# MCU.net
KiCad netlist of a schematic drawn in Altium Designer
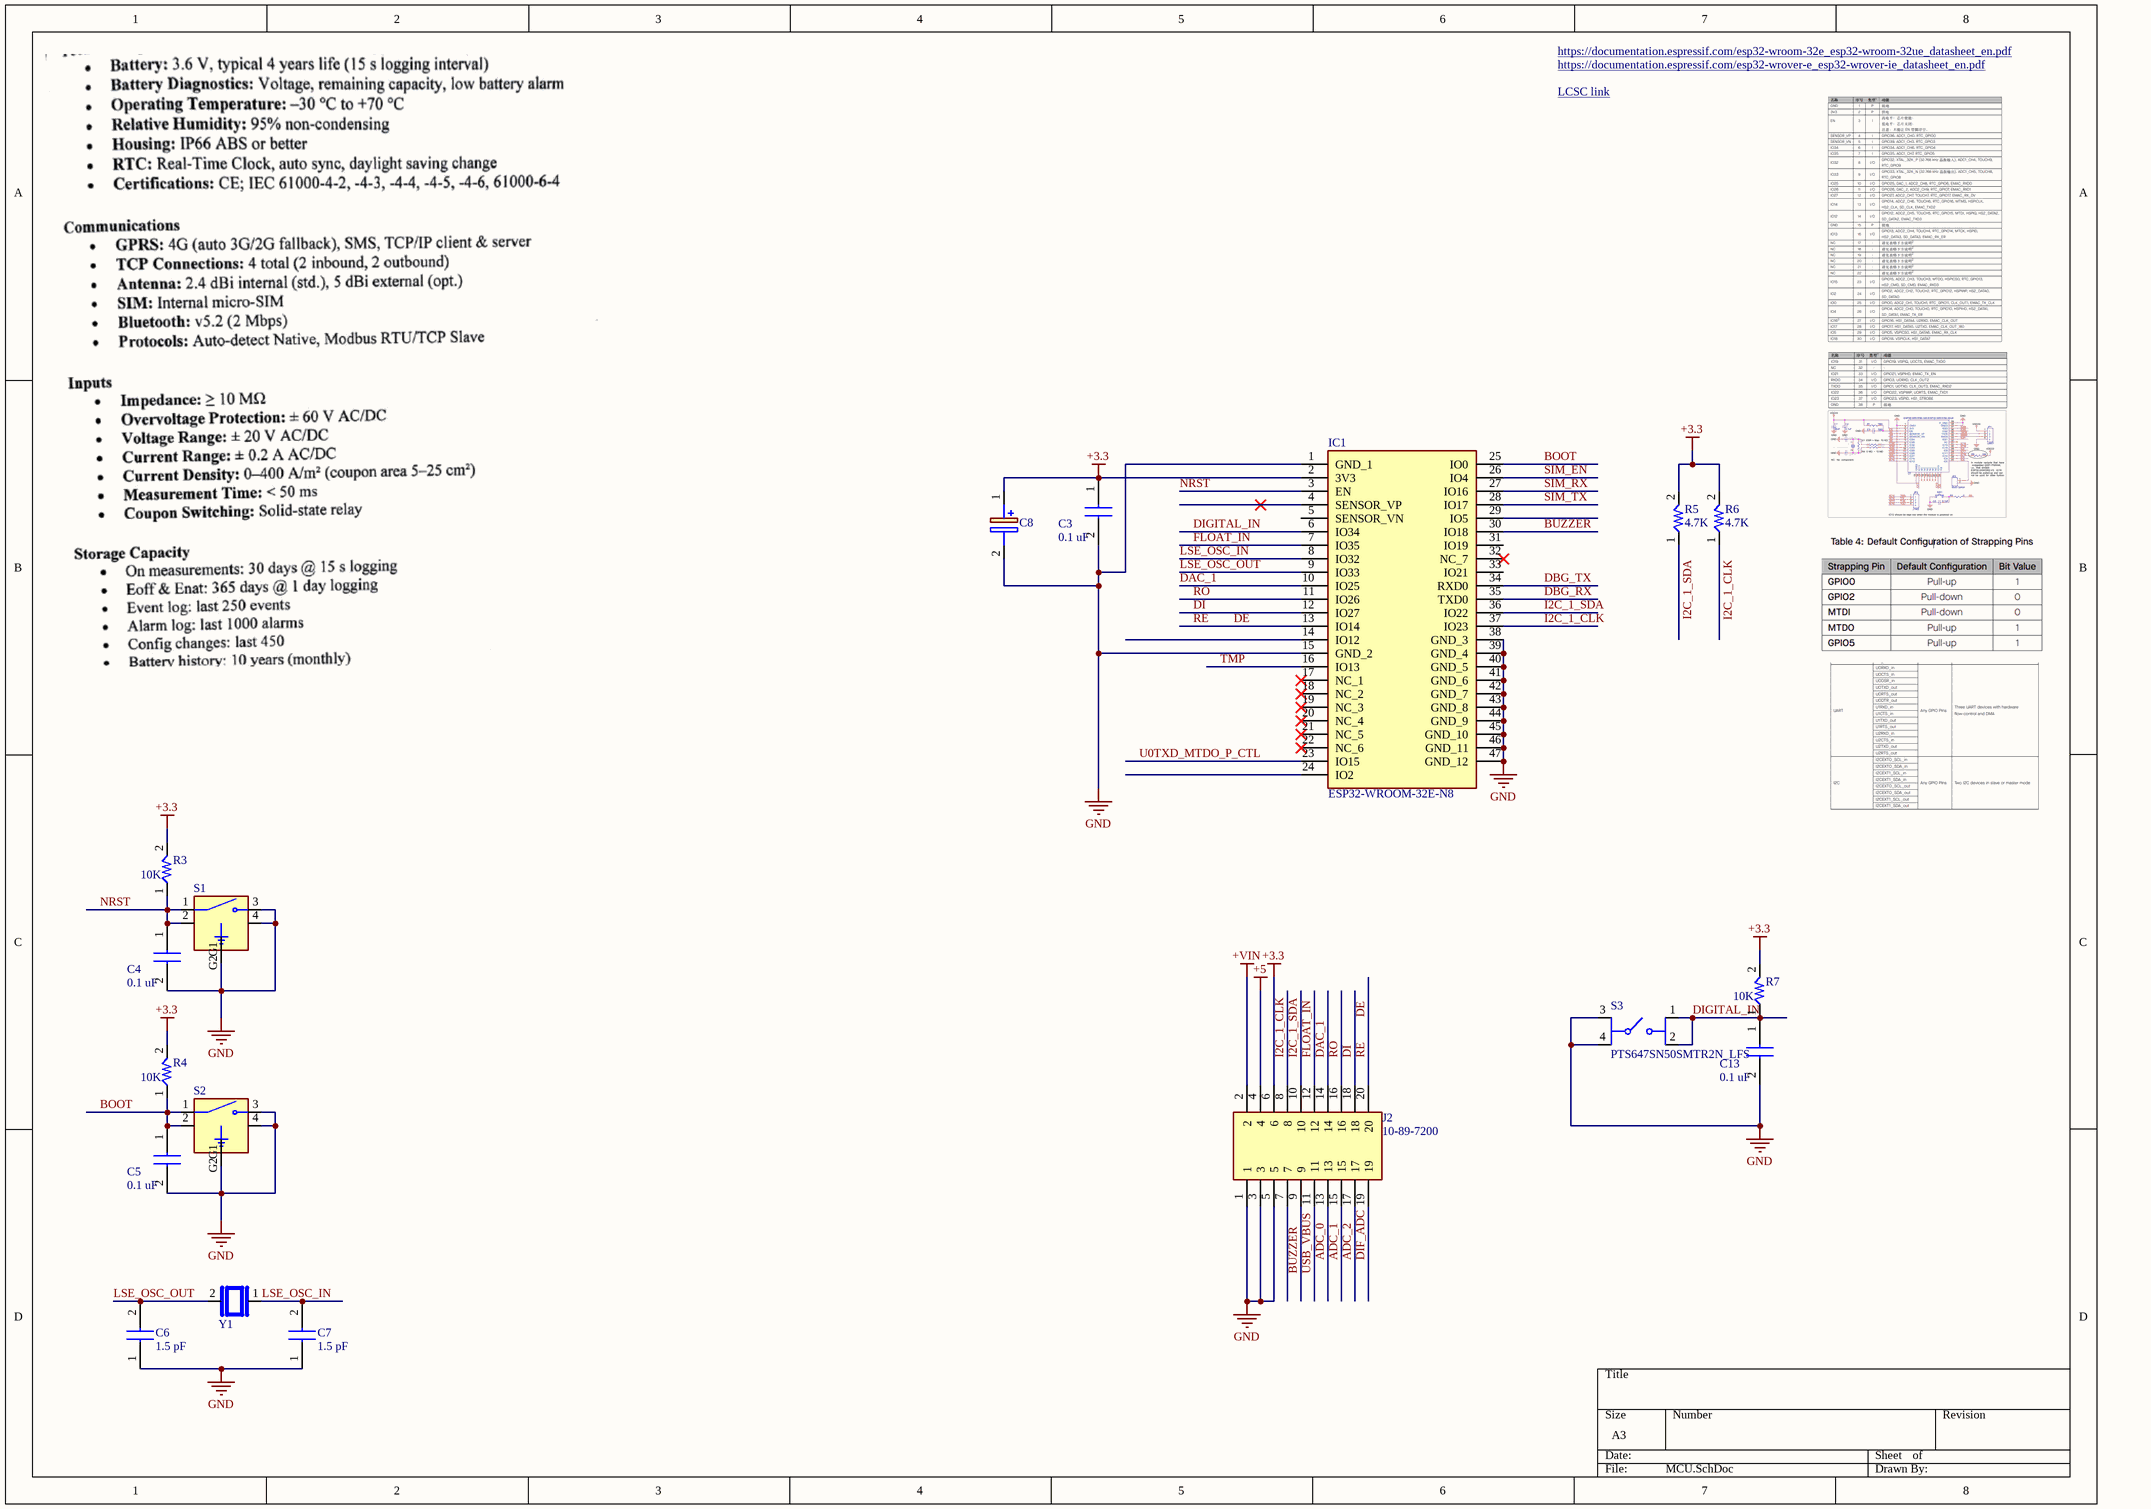
[diagram p0: MCU.SchDoc]

(export (version "E")
  (design (tool "Eeschema 10.0.6"))
  (components
    (comp (ref "C3")
      (value "0.1 uF")
      (footprint "CAP0603")
      (description "Capacitor")
      (fields
        (field (name "MANUFACTURER_PART_NUMBER") "CC0603KRX7R9BB104")
        (field (name "MOUSER PART NUMBER") "603-CC603KRX7R9BB104")
      )
      (libsource (lib "Valve_Controller_Lib") (part "CC0603KRX7R9BB104"))
    )
    (comp (ref "C4")
      (value "0.1 uF")
      (footprint "CAP0603")
      (description "Capacitor")
      (fields
        (field (name "MANUFACTURER_PART_NUMBER") "CC0603KRX7R9BB104")
        (field (name "MOUSER PART NUMBER") "603-CC603KRX7R9BB104")
      )
      (libsource (lib "Valve_Controller_Lib") (part "CC0603KRX7R9BB104"))
    )
    (comp (ref "C5")
      (value "0.1 uF")
      (footprint "CAP0603")
      (description "Capacitor")
      (fields
        (field (name "MANUFACTURER_PART_NUMBER") "CC0603KRX7R9BB104")
        (field (name "MOUSER PART NUMBER") "603-CC603KRX7R9BB104")
      )
      (libsource (lib "Valve_Controller_Lib") (part "CC0603KRX7R9BB104"))
    )
    (comp (ref "C6")
      (value "1.5 pF")
      (footprint "CAP0603")
      (description "Capacitor")
      (fields
        (field (name "MANUFACTURER_PART_NUMBER") "CC0603KRX7R9BB104")
        (field (name "MOUSER PART NUMBER") "603-CC603KRX7R9BB104")
      )
      (libsource (lib "Valve_Controller_Lib") (part "CC0603KRX7R9BB104"))
    )
    (comp (ref "C7")
      (value "1.5 pF")
      (footprint "CAP0603")
      (description "Capacitor")
      (fields
        (field (name "MANUFACTURER_PART_NUMBER") "CC0603KRX7R9BB104")
        (field (name "MOUSER PART NUMBER") "603-CC603KRX7R9BB104")
      )
      (libsource (lib "Valve_Controller_Lib") (part "CC0603KRX7R9BB104"))
    )
    (comp (ref "C8")
      (value "TPSD227K010R0100")
      (footprint "SamacSys:CAPPM7344X310N")
      (description "Capacitor Polarised")
      (fields (field (name "MOUSER PART NUMBER") "581-TPSD227K010R0100"))
      (libsource (lib "*") (part "TPSD227K010R0100"))
    )
    (comp (ref "C13")
      (value "0.1 uF")
      (footprint "CAP0603")
      (description "Capacitor")
      (fields
        (field (name "MANUFACTURER_PART_NUMBER") "CC0603KRX7R9BB104")
        (field (name "MOUSER PART NUMBER") "603-CC603KRX7R9BB104")
      )
      (libsource (lib "Valve_Controller_Lib") (part "CC0603KRX7R9BB104"))
    )
    (comp (ref "IC1")
      (value "ESP32-WROOM-32E-N8")
      (footprint "SamacSys:ESP32WROOM32EN8")
      (description "Integrated Circuit")
      (fields (field (name "MOUSER PART NUMBER") "356-ESP32WRM32E164PH"))
      (libsource (lib "*") (part "ESP32-WROOM-32E-N8"))
    )
    (comp (ref "J2")
      (value "10-89-7200")
      (footprint "SamacSys:HDRV20W87P254_2X10_2553X508X864P")
      (description "Connector")
      (fields (field (name "MOUSER PART NUMBER") "538-10-89-7200"))
      (libsource (lib "*") (part "10-89-7200"))
    )
    (comp (ref "R3")
      (value "10K")
      (footprint "RES0603")
      (description "Resistor")
      (fields (field (name "MANUFACTURER_PART_NUMBER") "0603WAF1001T5E"))
      (libsource (lib "Valve_Controller_Lib") (part "RES"))
    )
    (comp (ref "R4")
      (value "10K")
      (footprint "RES0603")
      (description "Resistor")
      (fields (field (name "MANUFACTURER_PART_NUMBER") "0603WAF1001T5E"))
      (libsource (lib "Valve_Controller_Lib") (part "RES"))
    )
    (comp (ref "R5")
      (value "4.7K")
      (footprint "RES0603")
      (description "Resistor")
      (fields (field (name "MANUFACTURER_PART_NUMBER") "0603WAF1001T5E"))
      (libsource (lib "Valve_Controller_Lib") (part "RES"))
    )
    (comp (ref "R6")
      (value "4.7K")
      (footprint "RES0603")
      (description "Resistor")
      (fields (field (name "MANUFACTURER_PART_NUMBER") "0603WAF1001T5E"))
      (libsource (lib "Valve_Controller_Lib") (part "RES"))
    )
    (comp (ref "R7")
      (value "10K")
      (footprint "RES0603")
      (description "Resistor")
      (fields (field (name "MANUFACTURER_PART_NUMBER") "0603WAF1001T5E"))
      (libsource (lib "Valve_Controller_Lib") (part "RES"))
    )
    (comp (ref "S1")
      (value "PTS526_SMG15_SMTR2_LFS")
      (footprint "SW_PTS526_SMG15_SMTR2_LFS")
      (description "Tactile Switch SPST-NO Top Actuated Surface Mount")
      (fields (field (name "MP") "PTS526 SMG15 SMTR2 LFS") (field (name "MF") "C&K"))
      (libsource (lib "Valve_Controller_Lib") (part "PTS526_SMG15_SMTR2_LFS"))
    )
    (comp (ref "S2")
      (value "PTS526_SMG15_SMTR2_LFS")
      (footprint "SW_PTS526_SMG15_SMTR2_LFS")
      (description "Tactile Switch SPST-NO Top Actuated Surface Mount")
      (fields (field (name "MP") "PTS526 SMG15 SMTR2 LFS") (field (name "MF") "C&K"))
      (libsource (lib "Valve_Controller_Lib") (part "PTS526_SMG15_SMTR2_LFS"))
    )
    (comp (ref "S3")
      (value "PTS647SN50SMTR2N_LFS")
      (footprint "SamacSys:PTS647SK50SMTR2LFS")
      (description "Switch (4-Pin Push)")
      (fields (field (name "MANUFACTURER_PART_NUMBER") "PTS647SN50SMTR2N LFS"))
      (libsource (lib "*") (part "PTS647SN50SMTR2N_LFS"))
    )
    (comp (ref "Y1")
      (value "CM8V-T1A-32.768KHZ-6PF-20PPM-TA-QC")
      (footprint "XTAL_CM8V-T1A-32.768KHZ-6PF-20PPM-TA-QC")
      (description "Tuning Fork Crystal 32.768kHz in SMD 1.2 x 2.0mm package")
      (fields (field (name "MF") "Micro Crystal") (field (name "MP") "CM8V-T1A-32.768kHz-6pF-20PPM-TA-QC"))
      (libsource (lib "Valve_Controller_Lib") (part "CM8V-T1A-32.768KHZ-6PF-20PPM-TA-QC"))
    )
  )
  (nets
    (net (code "1") (name "+3.3") (class "Default")
      (node (ref "C3") (pin "1") (pinfunction "1_1") (pintype "passive"))
      (node (ref "C8") (pin "1") (pinfunction "+_1") (pintype "passive"))
      (node (ref "IC1") (pin "2") (pinfunction "3V3_2") (pintype "passive"))
      (node (ref "J2") (pin "6") (pinfunction "6_6") (pintype "passive"))
      (node (ref "R3") (pin "2") (pinfunction "2_2") (pintype "passive"))
      (node (ref "R4") (pin "2") (pinfunction "2_2") (pintype "passive"))
      (node (ref "R5") (pin "2") (pinfunction "2_2") (pintype "passive"))
      (node (ref "R6") (pin "2") (pinfunction "2_2") (pintype "passive"))
      (node (ref "R7") (pin "2") (pinfunction "2_2") (pintype "passive"))
    )
    (net (code "2") (name "+5") (class "Default")
      (node (ref "J2") (pin "4") (pinfunction "4_4") (pintype "passive"))
    )
    (net (code "3") (name "+VIN") (class "Default")
      (node (ref "J2") (pin "2") (pinfunction "2_2") (pintype "passive"))
    )
    (net (code "4") (name "/ADC_0") (class "Default")
      (node (ref "J2") (pin "13") (pinfunction "13_13") (pintype "passive"))
    )
    (net (code "5") (name "/ADC_1") (class "Default")
      (node (ref "J2") (pin "15") (pinfunction "15_15") (pintype "passive"))
    )
    (net (code "6") (name "/ADC_2") (class "Default")
      (node (ref "J2") (pin "17") (pinfunction "17_17") (pintype "passive"))
    )
    (net (code "7") (name "/BOOT") (class "Default")
      (node (ref "C5") (pin "1") (pinfunction "1_1") (pintype "passive"))
      (node (ref "IC1") (pin "25") (pinfunction "IO0_25") (pintype "passive"))
      (node (ref "R4") (pin "1") (pinfunction "1_1") (pintype "passive"))
      (node (ref "S2") (pin "1") (pinfunction "COM_1") (pintype "passive"))
      (node (ref "S2") (pin "2") (pinfunction "COM_2") (pintype "passive"))
    )
    (net (code "8") (name "/BUZZER") (class "Default")
      (node (ref "IC1") (pin "30") (pinfunction "IO18_30") (pintype "passive"))
      (node (ref "J2") (pin "9") (pinfunction "9_9") (pintype "passive"))
    )
    (net (code "9") (name "/DAC_1") (class "Default")
      (node (ref "IC1") (pin "10") (pinfunction "IO25_10") (pintype "passive"))
      (node (ref "J2") (pin "14") (pinfunction "14_14") (pintype "passive"))
    )
    (net (code "10") (name "/DBG_RX") (class "Default")
      (node (ref "IC1") (pin "35") (pinfunction "TXD0_35") (pintype "passive"))
    )
    (net (code "11") (name "/DBG_TX") (class "Default")
      (node (ref "IC1") (pin "34") (pinfunction "RXD0_34") (pintype "passive"))
    )
    (net (code "12") (name "/DE") (class "Default")
      (node (ref "IC1") (pin "13") (pinfunction "IO14_13") (pintype "passive"))
      (node (ref "J2") (pin "20") (pinfunction "20_20") (pintype "passive"))
    )
    (net (code "13") (name "/DI") (class "Default")
      (node (ref "IC1") (pin "12") (pinfunction "IO27_12") (pintype "passive"))
      (node (ref "J2") (pin "18") (pinfunction "18_18") (pintype "passive"))
    )
    (net (code "14") (name "/DIF_ADC") (class "Default")
      (node (ref "J2") (pin "19") (pinfunction "19_19") (pintype "passive"))
    )
    (net (code "15") (name "/DIGITAL_IN") (class "Default")
      (node (ref "C13") (pin "1") (pinfunction "1_1") (pintype "passive"))
      (node (ref "IC1") (pin "6") (pinfunction "IO34_6") (pintype "passive"))
      (node (ref "R7") (pin "1") (pinfunction "1_1") (pintype "passive"))
      (node (ref "S3") (pin "1") (pinfunction "NO_1_1") (pintype "passive"))
      (node (ref "S3") (pin "2") (pinfunction "NO_2_2") (pintype "passive"))
    )
    (net (code "16") (name "/FLOAT_IN") (class "Default")
      (node (ref "IC1") (pin "7") (pinfunction "IO35_7") (pintype "passive"))
      (node (ref "J2") (pin "12") (pinfunction "12_12") (pintype "passive"))
    )
    (net (code "17") (name "/I2C_1_CLK") (class "Default")
      (node (ref "IC1") (pin "37") (pinfunction "IO23_37") (pintype "passive"))
      (node (ref "J2") (pin "8") (pinfunction "8_8") (pintype "passive"))
      (node (ref "R6") (pin "1") (pinfunction "1_1") (pintype "passive"))
    )
    (net (code "18") (name "/I2C_1_SDA") (class "Default")
      (node (ref "IC1") (pin "36") (pinfunction "IO22_36") (pintype "passive"))
      (node (ref "J2") (pin "10") (pinfunction "10_10") (pintype "passive"))
      (node (ref "R5") (pin "1") (pinfunction "1_1") (pintype "passive"))
    )
    (net (code "19") (name "/LSE_OSC_IN") (class "Default")
      (node (ref "C7") (pin "2") (pinfunction "2_2") (pintype "passive"))
      (node (ref "IC1") (pin "8") (pinfunction "IO32_8") (pintype "passive"))
      (node (ref "Y1") (pin "1") (pinfunction "1_1") (pintype "passive"))
    )
    (net (code "20") (name "/LSE_OSC_OUT") (class "Default")
      (node (ref "C6") (pin "2") (pinfunction "2_2") (pintype "passive"))
      (node (ref "IC1") (pin "9") (pinfunction "IO33_9") (pintype "passive"))
      (node (ref "Y1") (pin "2") (pinfunction "2_2") (pintype "passive"))
    )
    (net (code "21") (name "/NRST") (class "Default")
      (node (ref "C4") (pin "1") (pinfunction "1_1") (pintype "passive"))
      (node (ref "IC1") (pin "3") (pinfunction "EN_3") (pintype "passive"))
      (node (ref "R3") (pin "1") (pinfunction "1_1") (pintype "passive"))
      (node (ref "S1") (pin "1") (pinfunction "COM_1") (pintype "passive"))
      (node (ref "S1") (pin "2") (pinfunction "COM_2") (pintype "passive"))
    )
    (net (code "22") (name "/RO") (class "Default")
      (node (ref "IC1") (pin "11") (pinfunction "IO26_11") (pintype "passive"))
      (node (ref "J2") (pin "16") (pinfunction "16_16") (pintype "passive"))
    )
    (net (code "23") (name "/SIM_EN") (class "Default")
      (node (ref "IC1") (pin "26") (pinfunction "IO4_26") (pintype "passive"))
    )
    (net (code "24") (name "/SIM_RX") (class "Default")
      (node (ref "IC1") (pin "27") (pinfunction "IO16_27") (pintype "passive"))
    )
    (net (code "25") (name "/SIM_TX") (class "Default")
      (node (ref "IC1") (pin "28") (pinfunction "IO17_28") (pintype "passive"))
    )
    (net (code "26") (name "/TMP") (class "Default")
      (node (ref "IC1") (pin "16") (pinfunction "IO13_16") (pintype "passive"))
    )
    (net (code "27") (name "/U0TXD_MTDO_P_CTL") (class "Default")
      (node (ref "IC1") (pin "23") (pinfunction "IO15_23") (pintype "passive"))
    )
    (net (code "28") (name "/USB_VBUS") (class "Default")
      (node (ref "J2") (pin "11") (pinfunction "11_11") (pintype "passive"))
    )
    (net (code "29") (name "GND") (class "Default")
      (node (ref "C13") (pin "2") (pinfunction "2_2") (pintype "passive"))
      (node (ref "C3") (pin "2") (pinfunction "2_2") (pintype "passive"))
      (node (ref "C4") (pin "2") (pinfunction "2_2") (pintype "passive"))
      (node (ref "C5") (pin "2") (pinfunction "2_2") (pintype "passive"))
      (node (ref "C6") (pin "1") (pinfunction "1_1") (pintype "passive"))
      (node (ref "C7") (pin "1") (pinfunction "1_1") (pintype "passive"))
      (node (ref "C8") (pin "2") (pinfunction "-_2") (pintype "passive"))
      (node (ref "IC1") (pin "1") (pinfunction "GND_1_1") (pintype "passive"))
      (node (ref "IC1") (pin "15") (pinfunction "GND_2_15") (pintype "passive"))
      (node (ref "IC1") (pin "38") (pinfunction "GND_3_38") (pintype "passive"))
      (node (ref "IC1") (pin "39") (pinfunction "GND_4_39") (pintype "passive"))
      (node (ref "IC1") (pin "40") (pinfunction "GND_5_40") (pintype "passive"))
      (node (ref "IC1") (pin "41") (pinfunction "GND_6_41") (pintype "passive"))
      (node (ref "IC1") (pin "42") (pinfunction "GND_7_42") (pintype "passive"))
      (node (ref "IC1") (pin "43") (pinfunction "GND_8_43") (pintype "passive"))
      (node (ref "IC1") (pin "44") (pinfunction "GND_9_44") (pintype "passive"))
      (node (ref "IC1") (pin "45") (pinfunction "GND_10_45") (pintype "passive"))
      (node (ref "IC1") (pin "46") (pinfunction "GND_11_46") (pintype "passive"))
      (node (ref "IC1") (pin "47") (pinfunction "GND_12_47") (pintype "passive"))
      (node (ref "J2") (pin "1") (pinfunction "1_1") (pintype "passive"))
      (node (ref "J2") (pin "3") (pinfunction "3_3") (pintype "passive"))
      (node (ref "J2") (pin "5") (pinfunction "5_5") (pintype "passive"))
      (node (ref "S1") (pin "3") (pinfunction "NO_3") (pintype "passive"))
      (node (ref "S1") (pin "4") (pinfunction "NO_4") (pintype "passive"))
      (node (ref "S1") (pin "G2") (pinfunction "GND_G2") (pintype "power_in"))
      (node (ref "S2") (pin "3") (pinfunction "NO_3") (pintype "passive"))
      (node (ref "S2") (pin "4") (pinfunction "NO_4") (pintype "passive"))
      (node (ref "S2") (pin "G2") (pinfunction "GND_G2") (pintype "power_in"))
      (node (ref "S3") (pin "3") (pinfunction "COM_1_3") (pintype "passive"))
      (node (ref "S3") (pin "4") (pinfunction "COM_2_4") (pintype "passive"))
    )
    (net (code "30") (name "unconnected-(IC1-IO2-Pad24)") (class "Default")
      (node (ref "IC1") (pin "24") (pinfunction "IO2_24") (pintype "passive"))
    )
    (net (code "31") (name "unconnected-(IC1-IO5-Pad29)") (class "Default")
      (node (ref "IC1") (pin "29") (pinfunction "IO5_29") (pintype "passive"))
    )
    (net (code "32") (name "unconnected-(IC1-IO12-Pad14)") (class "Default")
      (node (ref "IC1") (pin "14") (pinfunction "IO12_14") (pintype "passive"))
    )
    (net (code "33") (name "unconnected-(IC1-IO19-Pad31)") (class "Default")
      (node (ref "IC1") (pin "31") (pinfunction "IO19_31") (pintype "passive"))
    )
    (net (code "34") (name "unconnected-(IC1-IO21-Pad33)") (class "Default")
      (node (ref "IC1") (pin "33") (pinfunction "IO21_33") (pintype "passive"))
    )
    (net (code "35") (name "unconnected-(IC1-NC_1-Pad17)") (class "Default")
      (node (ref "IC1") (pin "17") (pinfunction "NC_1_17") (pintype "passive+no_connect"))
    )
    (net (code "36") (name "unconnected-(IC1-NC_2-Pad18)") (class "Default")
      (node (ref "IC1") (pin "18") (pinfunction "NC_2_18") (pintype "passive+no_connect"))
    )
    (net (code "37") (name "unconnected-(IC1-NC_3-Pad19)") (class "Default")
      (node (ref "IC1") (pin "19") (pinfunction "NC_3_19") (pintype "passive+no_connect"))
    )
    (net (code "38") (name "unconnected-(IC1-NC_4-Pad20)") (class "Default")
      (node (ref "IC1") (pin "20") (pinfunction "NC_4_20") (pintype "passive+no_connect"))
    )
    (net (code "39") (name "unconnected-(IC1-NC_5-Pad21)") (class "Default")
      (node (ref "IC1") (pin "21") (pinfunction "NC_5_21") (pintype "passive+no_connect"))
    )
    (net (code "40") (name "unconnected-(IC1-NC_6-Pad22)") (class "Default")
      (node (ref "IC1") (pin "22") (pinfunction "NC_6_22") (pintype "passive+no_connect"))
    )
    (net (code "41") (name "unconnected-(IC1-NC_7-Pad32)") (class "Default")
      (node (ref "IC1") (pin "32") (pinfunction "NC_7_32") (pintype "passive+no_connect"))
    )
    (net (code "42") (name "unconnected-(IC1-SENSOR_VN-Pad5)") (class "Default")
      (node (ref "IC1") (pin "5") (pinfunction "SENSOR_VN_5") (pintype "passive"))
    )
    (net (code "43") (name "unconnected-(IC1-SENSOR_VP-Pad4)") (class "Default")
      (node (ref "IC1") (pin "4") (pinfunction "SENSOR_VP_4") (pintype "passive"))
    )
    (net (code "44") (name "unconnected-(J2-Pad7)") (class "Default")
      (node (ref "J2") (pin "7") (pinfunction "7_7") (pintype "passive"))
    )
    (net (code "45") (name "unconnected-(S1-GND-PadG1)") (class "Default")
      (node (ref "S1") (pin "G1") (pinfunction "GND_G1") (pintype "power_in"))
    )
    (net (code "46") (name "unconnected-(S2-GND-PadG1)") (class "Default")
      (node (ref "S2") (pin "G1") (pinfunction "GND_G1") (pintype "power_in"))
    )
  )
)
